# FLEX_INPUTS.net
KiCad netlist of a schematic drawn in Altium Designer
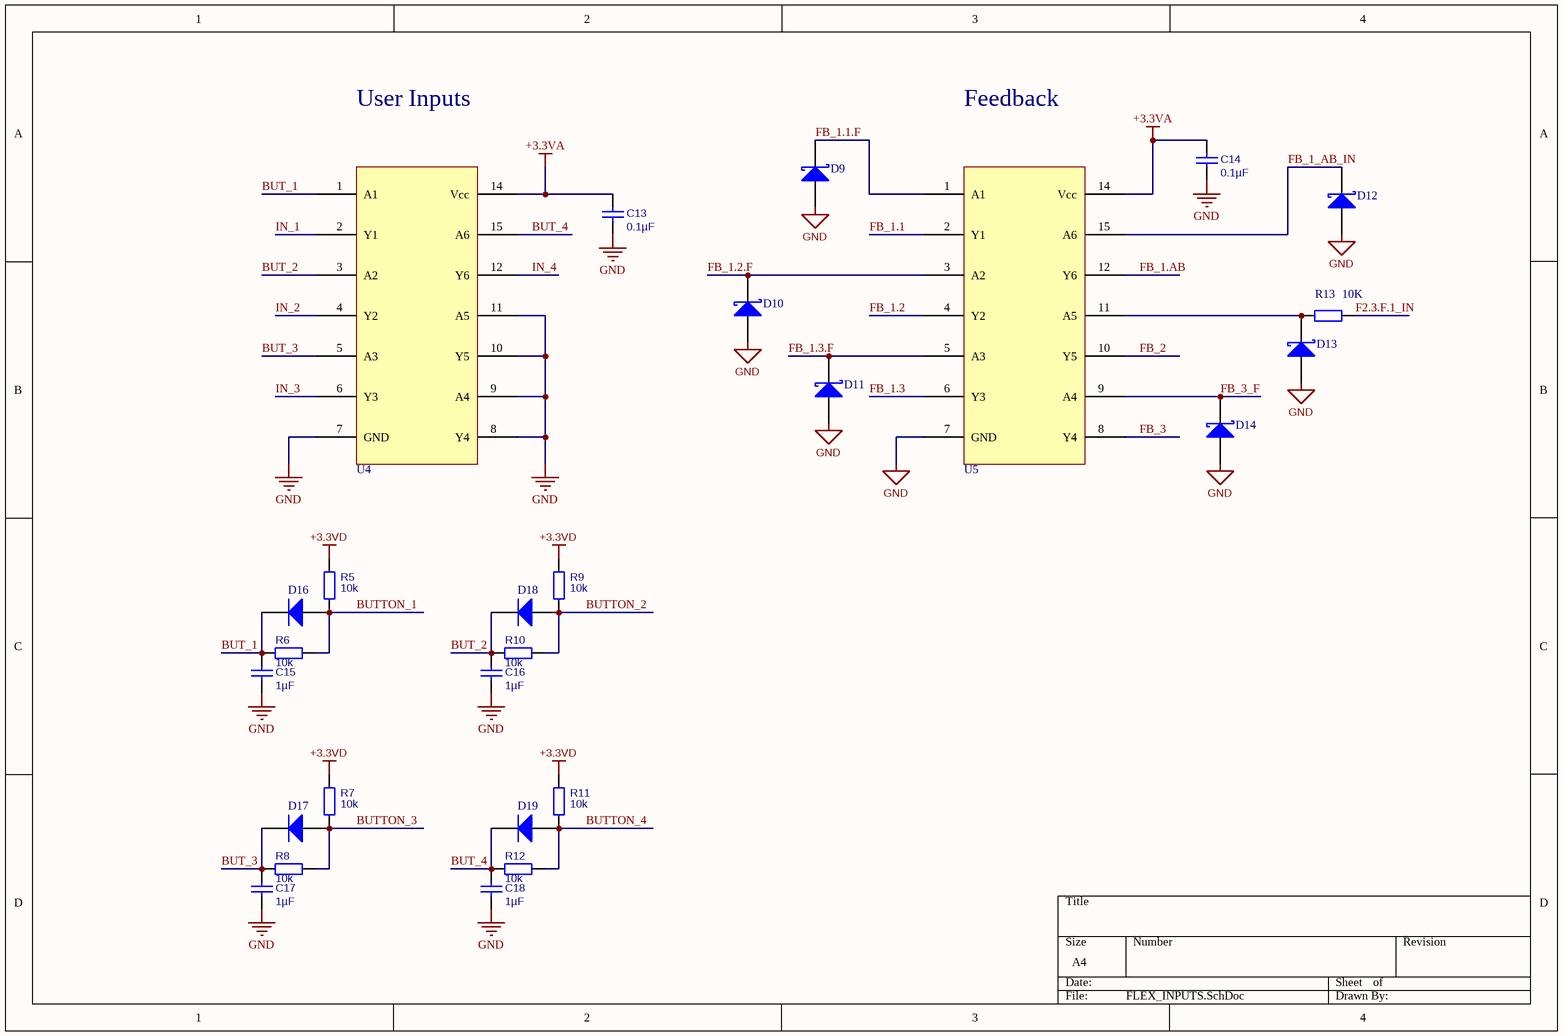
[diagram p0: FLEX_INPUTS.SchDoc]

(export (version "E")
  (design (tool "Eeschema 10.0.6"))
  (components
    (comp (ref "C13")
      (value "0.1µF")
      (footprint "TDK C-Series (1608)")
      (description "Capacitor")
      (fields (field (name "Comment") "Cap") (field (name "PUBLISHER") "Altium Limited"))
      (libsource (lib "Miscellaneous Devices") (part "Cap"))
    )
    (comp (ref "C14")
      (value "0.1µF")
      (footprint "TDK C-Series (1608)")
      (description "Capacitor")
      (fields (field (name "Comment") "Cap") (field (name "PUBLISHER") "Altium Limited"))
      (libsource (lib "Miscellaneous Devices") (part "Cap"))
    )
    (comp (ref "C15")
      (value "1µF")
      (footprint "TDK C-Series (1608)")
      (description "Capacitor")
      (fields (field (name "Comment") "Cap") (field (name "PUBLISHER") "Altium Limited"))
      (libsource (lib "Miscellaneous Devices") (part "Cap"))
    )
    (comp (ref "C16")
      (value "1µF")
      (footprint "TDK C-Series (1608)")
      (description "Capacitor")
      (fields (field (name "Comment") "Cap") (field (name "PUBLISHER") "Altium Limited"))
      (libsource (lib "Miscellaneous Devices") (part "Cap"))
    )
    (comp (ref "C17")
      (value "1µF")
      (footprint "TDK C-Series (1608)")
      (description "Capacitor")
      (fields (field (name "Comment") "Cap") (field (name "PUBLISHER") "Altium Limited"))
      (libsource (lib "Miscellaneous Devices") (part "Cap"))
    )
    (comp (ref "C18")
      (value "1µF")
      (footprint "TDK C-Series (1608)")
      (description "Capacitor")
      (fields (field (name "Comment") "Cap") (field (name "PUBLISHER") "Altium Limited"))
      (libsource (lib "Miscellaneous Devices") (part "Cap"))
    )
    (comp (ref "D9")
      (value "Diode BAT17")
      (footprint "Diode_TVS SODFL100X45-2N")
      (description "Silicon RF Schottky Diode for Mixer Applications in the VHF/UHF Range")
      (fields (field (name "PUBLISHER") "Altium Limited"))
      (libsource (lib "Miscellaneous Devices") (part "Diode BAT17"))
    )
    (comp (ref "D10")
      (value "Diode BAT17")
      (footprint "Diode_TVS SODFL100X45-2N")
      (description "Silicon RF Schottky Diode for Mixer Applications in the VHF/UHF Range")
      (fields (field (name "PUBLISHER") "Altium Limited"))
      (libsource (lib "Miscellaneous Devices") (part "Diode BAT17"))
    )
    (comp (ref "D11")
      (value "Diode BAT17")
      (footprint "Diode_TVS SODFL100X45-2N")
      (description "Silicon RF Schottky Diode for Mixer Applications in the VHF/UHF Range")
      (fields (field (name "PUBLISHER") "Altium Limited"))
      (libsource (lib "Miscellaneous Devices") (part "Diode BAT17"))
    )
    (comp (ref "D12")
      (value "Diode BAT17")
      (footprint "Diode_TVS SODFL100X45-2N")
      (description "Silicon RF Schottky Diode for Mixer Applications in the VHF/UHF Range")
      (fields (field (name "PUBLISHER") "Altium Limited"))
      (libsource (lib "Miscellaneous Devices") (part "Diode BAT17"))
    )
    (comp (ref "D13")
      (value "Diode BAT17")
      (footprint "Diode_TVS SODFL100X45-2N")
      (description "Silicon RF Schottky Diode for Mixer Applications in the VHF/UHF Range")
      (fields (field (name "PUBLISHER") "Altium Limited"))
      (libsource (lib "Miscellaneous Devices") (part "Diode BAT17"))
    )
    (comp (ref "D14")
      (value "Diode BAT17")
      (footprint "Diode_TVS SODFL100X45-2N")
      (description "Silicon RF Schottky Diode for Mixer Applications in the VHF/UHF Range")
      (fields (field (name "PUBLISHER") "Altium Limited"))
      (libsource (lib "Miscellaneous Devices") (part "Diode BAT17"))
    )
    (comp (ref "D16")
      (value "de")
      (footprint "Diode_Shottky")
      (description "Default Diode")
      (fields (field (name "PUBLISHER") "Altium Limited"))
      (libsource (lib "Miscellaneous Devices") (part "Diode"))
    )
    (comp (ref "D17")
      (value "de")
      (footprint "Diode_Shottky")
      (description "Default Diode")
      (fields (field (name "PUBLISHER") "Altium Limited"))
      (libsource (lib "Miscellaneous Devices") (part "Diode"))
    )
    (comp (ref "D18")
      (value "de")
      (footprint "Diode_Shottky")
      (description "Default Diode")
      (fields (field (name "PUBLISHER") "Altium Limited"))
      (libsource (lib "Miscellaneous Devices") (part "Diode"))
    )
    (comp (ref "D19")
      (value "de")
      (footprint "Diode_Shottky")
      (description "Default Diode")
      (fields (field (name "PUBLISHER") "Altium Limited"))
      (libsource (lib "Miscellaneous Devices") (part "Diode"))
    )
    (comp (ref "R5")
      (value "10k")
      (footprint "Panasonic ERJ-Series (1608)")
      (description "Resistor")
      (fields (field (name "PUBLISHER") "Altium Limited"))
      (libsource (lib "") (part "Res2_1"))
    )
    (comp (ref "R6")
      (value "10k")
      (footprint "Panasonic ERJ-Series (1608)")
      (description "Resistor")
      (fields (field (name "PUBLISHER") "Altium Limited"))
      (libsource (lib "Miscellaneous Devices") (part "Res2"))
    )
    (comp (ref "R7")
      (value "10k")
      (footprint "Panasonic ERJ-Series (1608)")
      (description "Resistor")
      (fields (field (name "PUBLISHER") "Altium Limited"))
      (libsource (lib "") (part "Res2_1"))
    )
    (comp (ref "R8")
      (value "10k")
      (footprint "Panasonic ERJ-Series (1608)")
      (description "Resistor")
      (fields (field (name "PUBLISHER") "Altium Limited"))
      (libsource (lib "Miscellaneous Devices") (part "Res2"))
    )
    (comp (ref "R9")
      (value "10k")
      (footprint "Panasonic ERJ-Series (1608)")
      (description "Resistor")
      (fields (field (name "PUBLISHER") "Altium Limited"))
      (libsource (lib "") (part "Res2_1"))
    )
    (comp (ref "R10")
      (value "10k")
      (footprint "Panasonic ERJ-Series (1608)")
      (description "Resistor")
      (fields (field (name "PUBLISHER") "Altium Limited"))
      (libsource (lib "Miscellaneous Devices") (part "Res2"))
    )
    (comp (ref "R11")
      (value "10k")
      (footprint "Panasonic ERJ-Series (1608)")
      (description "Resistor")
      (fields (field (name "PUBLISHER") "Altium Limited"))
      (libsource (lib "") (part "Res2_1"))
    )
    (comp (ref "R12")
      (value "10k")
      (footprint "Panasonic ERJ-Series (1608)")
      (description "Resistor")
      (fields (field (name "PUBLISHER") "Altium Limited"))
      (libsource (lib "Miscellaneous Devices") (part "Res2"))
    )
    (comp (ref "R13")
      (value "10K")
      (footprint "Panasonic ERJ-Series (1608)")
      (description "Resistor")
      (fields (field (name "PUBLISHER") "Altium Limited"))
      (libsource (lib "") (part "Res2_1"))
    )
    (comp (ref "U4")
      (value "MC74VHCT50A")
      (description "6-Channel CMOS Buffer")
      (libsource (lib "Schematics Library") (part "MC74VHCT50A"))
    )
    (comp (ref "U5")
      (value "MC74VHCT50A")
      (description "6-Channel CMOS Buffer")
      (libsource (lib "Schematics Library") (part "MC74VHCT50A"))
    )
  )
  (nets
    (net (code "1") (name "+3.3VA") (class "Default")
      (node (ref "C13") (pin "2") (pinfunction "2_2") (pintype "passive"))
      (node (ref "C14") (pin "2") (pinfunction "2_2") (pintype "passive"))
      (node (ref "U4") (pin "14") (pinfunction "Vcc_14") (pintype "power_in"))
      (node (ref "U5") (pin "14") (pinfunction "Vcc_14") (pintype "power_in"))
    )
    (net (code "2") (name "+3.3VD") (class "Default")
      (node (ref "R11") (pin "1") (pinfunction "1_1") (pintype "passive"))
      (node (ref "R5") (pin "1") (pinfunction "1_1") (pintype "passive"))
      (node (ref "R7") (pin "1") (pinfunction "1_1") (pintype "passive"))
      (node (ref "R9") (pin "1") (pinfunction "1_1") (pintype "passive"))
    )
    (net (code "3") (name "/BUTTON_1") (class "Default")
      (node (ref "D16") (pin "1") (pinfunction "A_1") (pintype "passive"))
      (node (ref "R5") (pin "2") (pinfunction "2_2") (pintype "passive"))
      (node (ref "R6") (pin "2") (pinfunction "2_2") (pintype "passive"))
    )
    (net (code "4") (name "/BUTTON_2") (class "Default")
      (node (ref "D18") (pin "1") (pinfunction "A_1") (pintype "passive"))
      (node (ref "R10") (pin "2") (pinfunction "2_2") (pintype "passive"))
      (node (ref "R9") (pin "2") (pinfunction "2_2") (pintype "passive"))
    )
    (net (code "5") (name "/BUTTON_3") (class "Default")
      (node (ref "D17") (pin "1") (pinfunction "A_1") (pintype "passive"))
      (node (ref "R7") (pin "2") (pinfunction "2_2") (pintype "passive"))
      (node (ref "R8") (pin "2") (pinfunction "2_2") (pintype "passive"))
    )
    (net (code "6") (name "/BUTTON_4") (class "Default")
      (node (ref "D19") (pin "1") (pinfunction "A_1") (pintype "passive"))
      (node (ref "R11") (pin "2") (pinfunction "2_2") (pintype "passive"))
      (node (ref "R12") (pin "2") (pinfunction "2_2") (pintype "passive"))
    )
    (net (code "7") (name "/BUT_1") (class "Default")
      (node (ref "C15") (pin "2") (pinfunction "2_2") (pintype "passive"))
      (node (ref "D16") (pin "2") (pinfunction "K_2") (pintype "passive"))
      (node (ref "R6") (pin "1") (pinfunction "1_1") (pintype "passive"))
      (node (ref "U4") (pin "1") (pinfunction "A1_1") (pintype "power_in"))
    )
    (net (code "8") (name "/BUT_2") (class "Default")
      (node (ref "C16") (pin "2") (pinfunction "2_2") (pintype "passive"))
      (node (ref "D18") (pin "2") (pinfunction "K_2") (pintype "passive"))
      (node (ref "R10") (pin "1") (pinfunction "1_1") (pintype "passive"))
      (node (ref "U4") (pin "3") (pinfunction "A2_3") (pintype "power_in"))
    )
    (net (code "9") (name "/BUT_3") (class "Default")
      (node (ref "C17") (pin "2") (pinfunction "2_2") (pintype "passive"))
      (node (ref "D17") (pin "2") (pinfunction "K_2") (pintype "passive"))
      (node (ref "R8") (pin "1") (pinfunction "1_1") (pintype "passive"))
      (node (ref "U4") (pin "5") (pinfunction "A3_5") (pintype "power_in"))
    )
    (net (code "10") (name "/BUT_4") (class "Default")
      (node (ref "C18") (pin "2") (pinfunction "2_2") (pintype "passive"))
      (node (ref "D19") (pin "2") (pinfunction "K_2") (pintype "passive"))
      (node (ref "R12") (pin "1") (pinfunction "1_1") (pintype "passive"))
      (node (ref "U4") (pin "15") (pinfunction "A6_15") (pintype "power_in"))
    )
    (net (code "11") (name "/F2.3.F.1_IN") (class "Default")
      (node (ref "R13") (pin "1") (pinfunction "1_1") (pintype "passive"))
    )
    (net (code "12") (name "/FB_1.1") (class "Default")
      (node (ref "U5") (pin "2") (pinfunction "Y1_2") (pintype "power_in"))
    )
    (net (code "13") (name "/FB_1.1.F") (class "Default")
      (node (ref "D9") (pin "3") (pinfunction "K_3") (pintype "passive"))
      (node (ref "U5") (pin "1") (pinfunction "A1_1") (pintype "power_in"))
    )
    (net (code "14") (name "/FB_1.2") (class "Default")
      (node (ref "U5") (pin "4") (pinfunction "Y2_4") (pintype "power_in"))
    )
    (net (code "15") (name "/FB_1.2.F") (class "Default")
      (node (ref "D10") (pin "3") (pinfunction "K_3") (pintype "passive"))
      (node (ref "U5") (pin "3") (pinfunction "A2_3") (pintype "power_in"))
    )
    (net (code "16") (name "/FB_1.3") (class "Default")
      (node (ref "U5") (pin "6") (pinfunction "Y3_6") (pintype "power_in"))
    )
    (net (code "17") (name "/FB_1.3.F") (class "Default")
      (node (ref "D11") (pin "3") (pinfunction "K_3") (pintype "passive"))
      (node (ref "U5") (pin "5") (pinfunction "A3_5") (pintype "power_in"))
    )
    (net (code "18") (name "/FB_1.AB") (class "Default")
      (node (ref "U5") (pin "12") (pinfunction "Y6_12") (pintype "power_in"))
    )
    (net (code "19") (name "/FB_1_AB_IN") (class "Default")
      (node (ref "D12") (pin "3") (pinfunction "K_3") (pintype "passive"))
      (node (ref "U5") (pin "15") (pinfunction "A6_15") (pintype "power_in"))
    )
    (net (code "20") (name "/FB_2") (class "Default")
      (node (ref "U5") (pin "10") (pinfunction "Y5_10") (pintype "power_in"))
    )
    (net (code "21") (name "/FB_3") (class "Default")
      (node (ref "U5") (pin "8") (pinfunction "Y4_8") (pintype "power_in"))
    )
    (net (code "22") (name "/FB_3_F") (class "Default")
      (node (ref "D14") (pin "3") (pinfunction "K_3") (pintype "passive"))
      (node (ref "U5") (pin "9") (pinfunction "A4_9") (pintype "power_in"))
    )
    (net (code "23") (name "/IN_1") (class "Default")
      (node (ref "U4") (pin "2") (pinfunction "Y1_2") (pintype "power_in"))
    )
    (net (code "24") (name "/IN_2") (class "Default")
      (node (ref "U4") (pin "4") (pinfunction "Y2_4") (pintype "power_in"))
    )
    (net (code "25") (name "/IN_3") (class "Default")
      (node (ref "U4") (pin "6") (pinfunction "Y3_6") (pintype "power_in"))
    )
    (net (code "26") (name "/IN_4") (class "Default")
      (node (ref "U4") (pin "12") (pinfunction "Y6_12") (pintype "power_in"))
    )
    (net (code "27") (name "GND") (class "Default")
      (node (ref "C13") (pin "1") (pinfunction "1_1") (pintype "passive"))
      (node (ref "C14") (pin "1") (pinfunction "1_1") (pintype "passive"))
      (node (ref "C15") (pin "1") (pinfunction "1_1") (pintype "passive"))
      (node (ref "C16") (pin "1") (pinfunction "1_1") (pintype "passive"))
      (node (ref "C17") (pin "1") (pinfunction "1_1") (pintype "passive"))
      (node (ref "C18") (pin "1") (pinfunction "1_1") (pintype "passive"))
      (node (ref "D10") (pin "1") (pinfunction "A_1") (pintype "passive"))
      (node (ref "D11") (pin "1") (pinfunction "A_1") (pintype "passive"))
      (node (ref "D12") (pin "1") (pinfunction "A_1") (pintype "passive"))
      (node (ref "D13") (pin "1") (pinfunction "A_1") (pintype "passive"))
      (node (ref "D14") (pin "1") (pinfunction "A_1") (pintype "passive"))
      (node (ref "D9") (pin "1") (pinfunction "A_1") (pintype "passive"))
      (node (ref "U4") (pin "10") (pinfunction "Y5_10") (pintype "power_in"))
      (node (ref "U4") (pin "11") (pinfunction "A5_11") (pintype "power_in"))
      (node (ref "U4") (pin "7") (pinfunction "GND_7") (pintype "power_in"))
      (node (ref "U4") (pin "8") (pinfunction "Y4_8") (pintype "power_in"))
      (node (ref "U4") (pin "9") (pinfunction "A4_9") (pintype "power_in"))
      (node (ref "U5") (pin "7") (pinfunction "GND_7") (pintype "power_in"))
    )
    (net (code "28") (name "Net-(D13-K)") (class "Default")
      (node (ref "D13") (pin "3") (pinfunction "K_3") (pintype "passive"))
      (node (ref "R13") (pin "2") (pinfunction "2_2") (pintype "passive"))
      (node (ref "U5") (pin "11") (pinfunction "A5_11") (pintype "power_in"))
    )
  )
)
